# MB_RELAY.net
KiCad netlist of a schematic drawn in Altium Designer
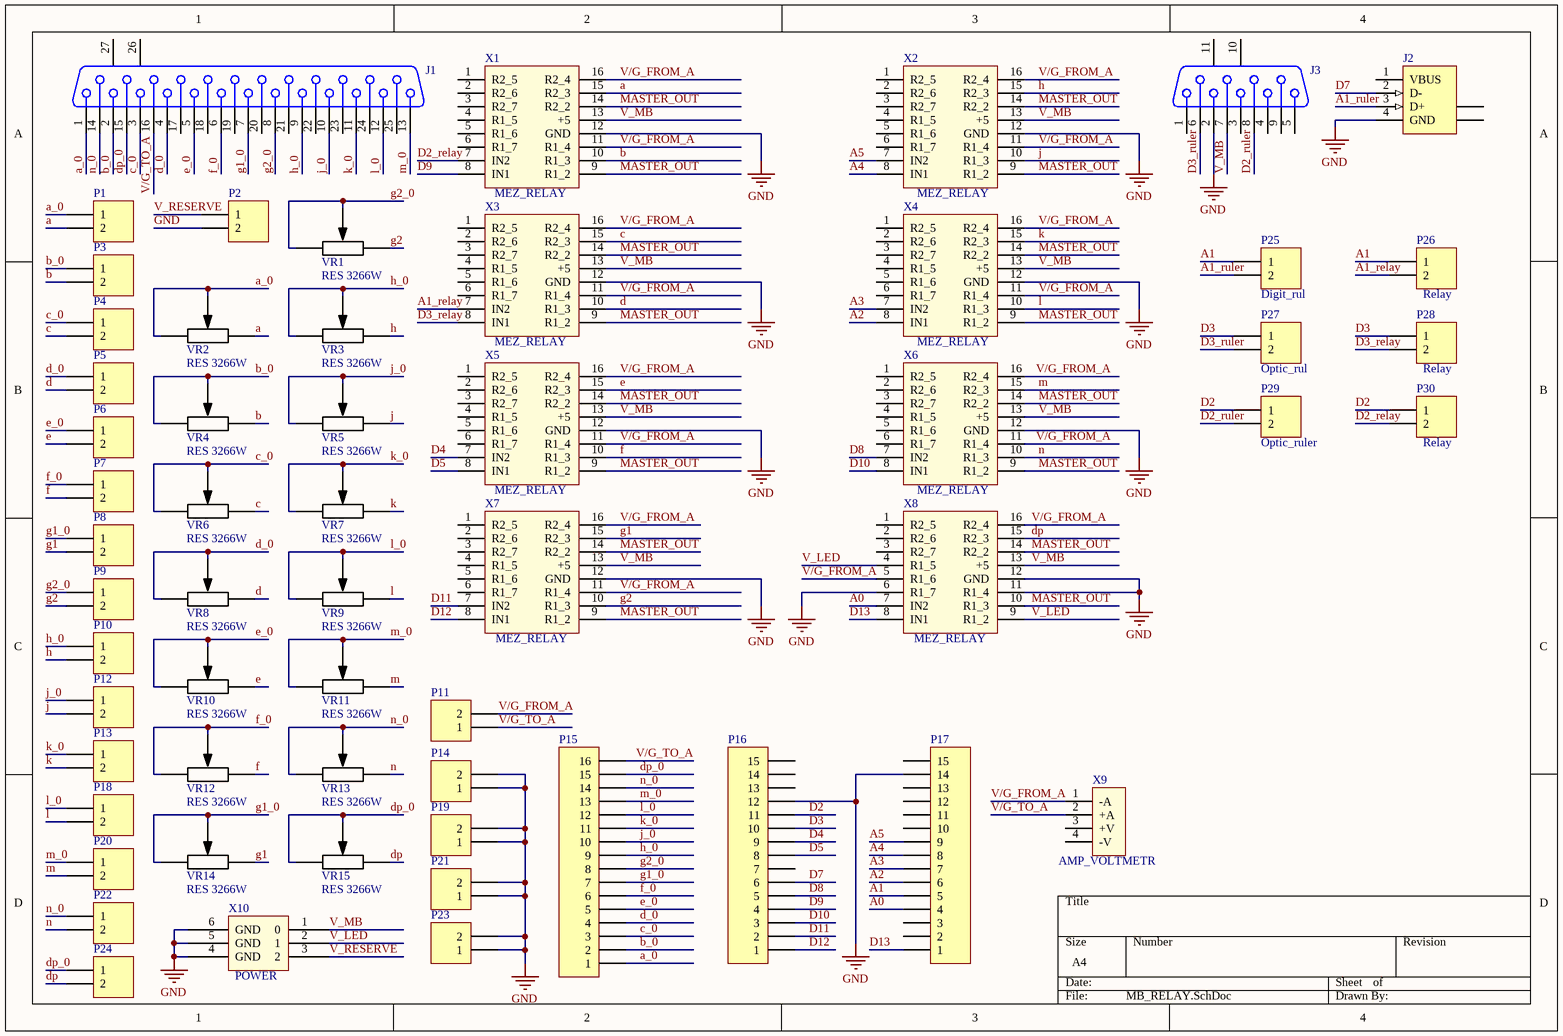
[diagram p0: MB_RELAY.SchDoc]

(export (version "E")
  (design (tool "Eeschema 10.0.6"))
  (components
    (comp (ref "J1")
      (value "D Connector 25")
      (footprint "DSUB1.385-2H25A")
      (description "Receptacle Assembly, 25 Position, Right Angle")
      (fields (field (name "PUBLISHER") "Altium Limited"))
      (libsource (lib "Miscellaneous Connectors") (part "D Connector 25"))
    )
    (comp (ref "J2")
      (value "1-353576-1")
      (footprint "353576")
      (description "USB 1.1, Right Angle, SMT, A Type, Receptacle, 4 Position, White")
      (fields (field (name "PUBLISHER") "Altium Limited"))
      (libsource (lib "AMP Serial Bus USB") (part "1-353576-1"))
    )
    (comp (ref "J3")
      (value "D Connector 9")
      (footprint "DSUB1.385-2H9")
      (description "Receptacle Assembly, 9 Position, Right Angle")
      (fields (field (name "PUBLISHER") "Altium Limited"))
      (libsource (lib "Miscellaneous Connectors") (part "D Connector 9"))
    )
    (comp (ref "P1")
      (value "Header 2")
      (footprint "HDR1X2")
      (description "Header, 2-Pin")
      (fields (field (name "PUBLISHER") "Altium Limited"))
      (libsource (lib "") (part "Header 2_1"))
    )
    (comp (ref "P2")
      (value "Header 2")
      (footprint "HDR1X2")
      (description "Header, 2-Pin")
      (fields (field (name "PUBLISHER") "Altium Limited"))
      (libsource (lib "") (part "Header 2_1"))
    )
    (comp (ref "P3")
      (value "Header 2")
      (footprint "HDR1X2")
      (description "Header, 2-Pin")
      (fields (field (name "PUBLISHER") "Altium Limited"))
      (libsource (lib "") (part "Header 2_1"))
    )
    (comp (ref "P4")
      (value "Header 2")
      (footprint "HDR1X2")
      (description "Header, 2-Pin")
      (fields (field (name "PUBLISHER") "Altium Limited"))
      (libsource (lib "") (part "Header 2_1"))
    )
    (comp (ref "P5")
      (value "Header 2")
      (footprint "HDR1X2")
      (description "Header, 2-Pin")
      (fields (field (name "PUBLISHER") "Altium Limited"))
      (libsource (lib "") (part "Header 2_1"))
    )
    (comp (ref "P6")
      (value "GND")
      (footprint "HDR1X2")
      (description "Header, 2-Pin")
      (fields (field (name "PUBLISHER") "Altium Limited"))
      (libsource (lib "") (part "Header 2_1"))
    )
    (comp (ref "P7")
      (value "GND")
      (footprint "HDR1X2")
      (description "Header, 2-Pin")
      (fields (field (name "PUBLISHER") "Altium Limited"))
      (libsource (lib "") (part "Header 2_1"))
    )
    (comp (ref "P8")
      (value "GND")
      (footprint "HDR1X2")
      (description "Header, 2-Pin")
      (fields (field (name "PUBLISHER") "Altium Limited"))
      (libsource (lib "") (part "Header 2_1"))
    )
    (comp (ref "P9")
      (value "GND")
      (footprint "HDR1X2")
      (description "Header, 2-Pin")
      (fields (field (name "PUBLISHER") "Altium Limited"))
      (libsource (lib "") (part "Header 2_1"))
    )
    (comp (ref "P10")
      (value "Header 2")
      (footprint "HDR1X2")
      (description "Header, 2-Pin")
      (fields (field (name "PUBLISHER") "Altium Limited"))
      (libsource (lib "") (part "Header 2_1"))
    )
    (comp (ref "P11")
      (value "Header 2")
      (footprint "HDR1X2")
      (description "Header, 2-Pin")
      (fields (field (name "PUBLISHER") "Altium Limited"))
      (libsource (lib "Miscellaneous Connectors") (part "Header 2"))
    )
    (comp (ref "P12")
      (value "Header 2")
      (footprint "HDR1X2")
      (description "Header, 2-Pin")
      (fields (field (name "PUBLISHER") "Altium Limited"))
      (libsource (lib "") (part "Header 2_1"))
    )
    (comp (ref "P13")
      (value "GND")
      (footprint "HDR1X2")
      (description "Header, 2-Pin")
      (fields (field (name "PUBLISHER") "Altium Limited"))
      (libsource (lib "") (part "Header 2_1"))
    )
    (comp (ref "P14")
      (value "GND")
      (footprint "HDR1X2")
      (description "Header, 2-Pin")
      (fields (field (name "PUBLISHER") "Altium Limited"))
      (libsource (lib "Miscellaneous Connectors") (part "Header 2"))
    )
    (comp (ref "P15")
      (value "Header 16")
      (footprint "HDR1X16")
      (description "Header, 16-Pin")
      (fields (field (name "PUBLISHER") "Altium Limited"))
      (libsource (lib "Miscellaneous Connectors") (part "Header 16"))
    )
    (comp (ref "P16")
      (value "Header 15")
      (footprint "HDR1X15")
      (description "Header, 15-Pin")
      (fields (field (name "PUBLISHER") "Altium Limited"))
      (libsource (lib "") (part "Header 15_1"))
    )
    (comp (ref "P17")
      (value "Header 15")
      (footprint "HDR1X15")
      (description "Header, 15-Pin")
      (fields (field (name "PUBLISHER") "Altium Limited"))
      (libsource (lib "Miscellaneous Connectors") (part "Header 15"))
    )
    (comp (ref "P18")
      (value "GND")
      (footprint "HDR1X2")
      (description "Header, 2-Pin")
      (fields (field (name "PUBLISHER") "Altium Limited"))
      (libsource (lib "") (part "Header 2_1"))
    )
    (comp (ref "P19")
      (value "GND")
      (footprint "HDR1X2")
      (description "Header, 2-Pin")
      (fields (field (name "PUBLISHER") "Altium Limited"))
      (libsource (lib "Miscellaneous Connectors") (part "Header 2"))
    )
    (comp (ref "P20")
      (value "GND")
      (footprint "HDR1X2")
      (description "Header, 2-Pin")
      (fields (field (name "PUBLISHER") "Altium Limited"))
      (libsource (lib "") (part "Header 2_1"))
    )
    (comp (ref "P21")
      (value "GND")
      (footprint "HDR1X2")
      (description "Header, 2-Pin")
      (fields (field (name "PUBLISHER") "Altium Limited"))
      (libsource (lib "Miscellaneous Connectors") (part "Header 2"))
    )
    (comp (ref "P22")
      (value "GND")
      (footprint "HDR1X2")
      (description "Header, 2-Pin")
      (fields (field (name "PUBLISHER") "Altium Limited"))
      (libsource (lib "") (part "Header 2_1"))
    )
    (comp (ref "P23")
      (value "GND")
      (footprint "HDR1X2")
      (description "Header, 2-Pin")
      (fields (field (name "PUBLISHER") "Altium Limited"))
      (libsource (lib "Miscellaneous Connectors") (part "Header 2"))
    )
    (comp (ref "P24")
      (value "GND")
      (footprint "HDR1X2")
      (description "Header, 2-Pin")
      (fields (field (name "PUBLISHER") "Altium Limited"))
      (libsource (lib "") (part "Header 2_1"))
    )
    (comp (ref "P25")
      (value "Digit_rul")
      (footprint "HDR1X2")
      (description "Header, 2-Pin")
      (fields (field (name "PUBLISHER") "Altium Limited"))
      (libsource (lib "") (part "Header 2_1"))
    )
    (comp (ref "P26")
      (value "Relay")
      (footprint "HDR1X2")
      (description "Header, 2-Pin")
      (fields (field (name "PUBLISHER") "Altium Limited"))
      (libsource (lib "") (part "Header 2_1"))
    )
    (comp (ref "P27")
      (value "Optic_rul")
      (footprint "HDR1X2")
      (description "Header, 2-Pin")
      (fields (field (name "PUBLISHER") "Altium Limited"))
      (libsource (lib "") (part "Header 2_1"))
    )
    (comp (ref "P28")
      (value "Relay")
      (footprint "HDR1X2")
      (description "Header, 2-Pin")
      (fields (field (name "PUBLISHER") "Altium Limited"))
      (libsource (lib "") (part "Header 2_1"))
    )
    (comp (ref "P29")
      (value "Optic_ruler")
      (footprint "HDR1X2")
      (description "Header, 2-Pin")
      (fields (field (name "PUBLISHER") "Altium Limited"))
      (libsource (lib "") (part "Header 2_1"))
    )
    (comp (ref "P30")
      (value "Relay")
      (footprint "HDR1X2")
      (description "Header, 2-Pin")
      (fields (field (name "PUBLISHER") "Altium Limited"))
      (libsource (lib "") (part "Header 2_1"))
    )
    (comp (ref "VR1")
      (value "RES 3266W")
      (footprint "aab_Passive:RES 3266W")
      (libsource (lib "aab_Schlib") (part "RES 3266W"))
    )
    (comp (ref "VR2")
      (value "RES 3266W")
      (footprint "aab_Passive:RES 3266W")
      (libsource (lib "aab_Schlib") (part "RES 3266W"))
    )
    (comp (ref "VR3")
      (value "RES 3266W")
      (footprint "aab_Passive:RES 3266W")
      (libsource (lib "aab_Schlib") (part "RES 3266W"))
    )
    (comp (ref "VR4")
      (value "RES 3266W")
      (footprint "aab_Passive:RES 3266W")
      (libsource (lib "aab_Schlib") (part "RES 3266W"))
    )
    (comp (ref "VR5")
      (value "RES 3266W")
      (footprint "aab_Passive:RES 3266W")
      (libsource (lib "aab_Schlib") (part "RES 3266W"))
    )
    (comp (ref "VR6")
      (value "RES 3266W")
      (footprint "aab_Passive:RES 3266W")
      (libsource (lib "aab_Schlib") (part "RES 3266W"))
    )
    (comp (ref "VR7")
      (value "RES 3266W")
      (footprint "aab_Passive:RES 3266W")
      (libsource (lib "aab_Schlib") (part "RES 3266W"))
    )
    (comp (ref "VR8")
      (value "RES 3266W")
      (footprint "aab_Passive:RES 3266W")
      (libsource (lib "aab_Schlib") (part "RES 3266W"))
    )
    (comp (ref "VR9")
      (value "RES 3266W")
      (footprint "aab_Passive:RES 3266W")
      (libsource (lib "aab_Schlib") (part "RES 3266W"))
    )
    (comp (ref "VR10")
      (value "RES 3266W")
      (footprint "aab_Passive:RES 3266W")
      (libsource (lib "aab_Schlib") (part "RES 3266W"))
    )
    (comp (ref "VR11")
      (value "RES 3266W")
      (footprint "aab_Passive:RES 3266W")
      (libsource (lib "aab_Schlib") (part "RES 3266W"))
    )
    (comp (ref "VR12")
      (value "RES 3266W")
      (footprint "aab_Passive:RES 3266W")
      (libsource (lib "aab_Schlib") (part "RES 3266W"))
    )
    (comp (ref "VR13")
      (value "RES 3266W")
      (footprint "aab_Passive:RES 3266W")
      (libsource (lib "aab_Schlib") (part "RES 3266W"))
    )
    (comp (ref "VR14")
      (value "RES 3266W")
      (footprint "aab_Passive:RES 3266W")
      (libsource (lib "aab_Schlib") (part "RES 3266W"))
    )
    (comp (ref "VR15")
      (value "RES 3266W")
      (footprint "aab_Passive:RES 3266W")
      (libsource (lib "aab_Schlib") (part "RES 3266W"))
    )
    (comp (ref "X1")
      (value "MEZ_RELAY")
      (footprint "MEZ_RELAY")
      (libsource (lib "msp_SchLib") (part "MEZ_RELAY"))
    )
    (comp (ref "X2")
      (value "MEZ_RELAY")
      (footprint "MEZ_RELAY")
      (libsource (lib "msp_SchLib") (part "MEZ_RELAY"))
    )
    (comp (ref "X3")
      (value "MEZ_RELAY")
      (footprint "MEZ_RELAY")
      (libsource (lib "msp_SchLib") (part "MEZ_RELAY"))
    )
    (comp (ref "X4")
      (value "MEZ_RELAY")
      (footprint "MEZ_RELAY")
      (libsource (lib "msp_SchLib") (part "MEZ_RELAY"))
    )
    (comp (ref "X5")
      (value "MEZ_RELAY")
      (footprint "MEZ_RELAY")
      (libsource (lib "msp_SchLib") (part "MEZ_RELAY"))
    )
    (comp (ref "X6")
      (value "MEZ_RELAY")
      (footprint "MEZ_RELAY")
      (libsource (lib "msp_SchLib") (part "MEZ_RELAY"))
    )
    (comp (ref "X7")
      (value "MEZ_RELAY")
      (footprint "MEZ_RELAY")
      (libsource (lib "msp_SchLib") (part "MEZ_RELAY"))
    )
    (comp (ref "X8")
      (value "MEZ_RELAY")
      (footprint "MEZ_RELAY")
      (libsource (lib "msp_SchLib") (part "MEZ_RELAY"))
    )
    (comp (ref "X9")
      (value "AMP_VOLTMETR")
      (footprint "vpl_Passive:AMP_VOLTMETER")
      (libsource (lib "msp_SchLib") (part "AMP_VOLTMETR"))
    )
    (comp (ref "X10")
      (value "POWER")
      (footprint "vpl_Passive:POWER")
      (libsource (lib "msp_SchLib") (part "POWER"))
    )
  )
  (nets
    (net (code "1") (name "/A0") (class "Default")
      (node (ref "P17") (pin "4") (pinfunction "4_4") (pintype "passive"))
      (node (ref "X8") (pin "7") (pinfunction "IN2_7") (pintype "passive"))
    )
    (net (code "2") (name "/A1") (class "Default")
      (node (ref "P17") (pin "5") (pinfunction "5_5") (pintype "passive"))
      (node (ref "P25") (pin "1") (pinfunction "1_1") (pintype "passive"))
      (node (ref "P26") (pin "1") (pinfunction "1_1") (pintype "passive"))
    )
    (net (code "3") (name "/A1_relay") (class "Default")
      (node (ref "P26") (pin "2") (pinfunction "2_2") (pintype "passive"))
      (node (ref "X3") (pin "7") (pinfunction "IN2_7") (pintype "passive"))
    )
    (net (code "4") (name "/A1_ruler") (class "Default")
      (node (ref "J2") (pin "3") (pinfunction "D+_3") (pintype "input"))
      (node (ref "P25") (pin "2") (pinfunction "2_2") (pintype "passive"))
    )
    (net (code "5") (name "/A2") (class "Default")
      (node (ref "P17") (pin "6") (pinfunction "6_6") (pintype "passive"))
      (node (ref "X4") (pin "8") (pinfunction "IN1_8") (pintype "passive"))
    )
    (net (code "6") (name "/A3") (class "Default")
      (node (ref "P17") (pin "7") (pinfunction "7_7") (pintype "passive"))
      (node (ref "X4") (pin "7") (pinfunction "IN2_7") (pintype "passive"))
    )
    (net (code "7") (name "/A4") (class "Default")
      (node (ref "P17") (pin "8") (pinfunction "8_8") (pintype "passive"))
      (node (ref "X2") (pin "8") (pinfunction "IN1_8") (pintype "passive"))
    )
    (net (code "8") (name "/A5") (class "Default")
      (node (ref "P17") (pin "9") (pinfunction "9_9") (pintype "passive"))
      (node (ref "X2") (pin "7") (pinfunction "IN2_7") (pintype "passive"))
    )
    (net (code "9") (name "/D2") (class "Default")
      (node (ref "P16") (pin "11") (pinfunction "11_11") (pintype "passive"))
      (node (ref "P29") (pin "1") (pinfunction "1_1") (pintype "passive"))
      (node (ref "P30") (pin "1") (pinfunction "1_1") (pintype "passive"))
    )
    (net (code "10") (name "/D2_relay") (class "Default")
      (node (ref "P30") (pin "2") (pinfunction "2_2") (pintype "passive"))
      (node (ref "X1") (pin "7") (pinfunction "IN2_7") (pintype "passive"))
    )
    (net (code "11") (name "/D2_ruler") (class "Default")
      (node (ref "J3") (pin "8") (pinfunction "8_8") (pintype "passive"))
      (node (ref "P29") (pin "2") (pinfunction "2_2") (pintype "passive"))
    )
    (net (code "12") (name "/D3") (class "Default")
      (node (ref "P16") (pin "10") (pinfunction "10_10") (pintype "passive"))
      (node (ref "P27") (pin "1") (pinfunction "1_1") (pintype "passive"))
      (node (ref "P28") (pin "1") (pinfunction "1_1") (pintype "passive"))
    )
    (net (code "13") (name "/D3_relay") (class "Default")
      (node (ref "P28") (pin "2") (pinfunction "2_2") (pintype "passive"))
      (node (ref "X3") (pin "8") (pinfunction "IN1_8") (pintype "passive"))
    )
    (net (code "14") (name "/D3_ruler") (class "Default")
      (node (ref "J3") (pin "6") (pinfunction "6_6") (pintype "passive"))
      (node (ref "P27") (pin "2") (pinfunction "2_2") (pintype "passive"))
    )
    (net (code "15") (name "/D4") (class "Default")
      (node (ref "P16") (pin "9") (pinfunction "9_9") (pintype "passive"))
      (node (ref "X5") (pin "7") (pinfunction "IN2_7") (pintype "passive"))
    )
    (net (code "16") (name "/D5") (class "Default")
      (node (ref "P16") (pin "8") (pinfunction "8_8") (pintype "passive"))
      (node (ref "X5") (pin "8") (pinfunction "IN1_8") (pintype "passive"))
    )
    (net (code "17") (name "/D7") (class "Default")
      (node (ref "J2") (pin "2") (pinfunction "D-_2") (pintype "input"))
      (node (ref "P16") (pin "6") (pinfunction "6_6") (pintype "passive"))
    )
    (net (code "18") (name "/D8") (class "Default")
      (node (ref "P16") (pin "5") (pinfunction "5_5") (pintype "passive"))
      (node (ref "X6") (pin "7") (pinfunction "IN2_7") (pintype "passive"))
    )
    (net (code "19") (name "/D9") (class "Default")
      (node (ref "P16") (pin "4") (pinfunction "4_4") (pintype "passive"))
      (node (ref "X1") (pin "8") (pinfunction "IN1_8") (pintype "passive"))
    )
    (net (code "20") (name "/D10") (class "Default")
      (node (ref "P16") (pin "3") (pinfunction "3_3") (pintype "passive"))
      (node (ref "X6") (pin "8") (pinfunction "IN1_8") (pintype "passive"))
    )
    (net (code "21") (name "/D11") (class "Default")
      (node (ref "P16") (pin "2") (pinfunction "2_2") (pintype "passive"))
      (node (ref "X7") (pin "7") (pinfunction "IN2_7") (pintype "passive"))
    )
    (net (code "22") (name "/D12") (class "Default")
      (node (ref "P16") (pin "1") (pinfunction "1_1") (pintype "passive"))
      (node (ref "X7") (pin "8") (pinfunction "IN1_8") (pintype "passive"))
    )
    (net (code "23") (name "/D13") (class "Default")
      (node (ref "P17") (pin "1") (pinfunction "1_1") (pintype "passive"))
      (node (ref "X8") (pin "8") (pinfunction "IN1_8") (pintype "passive"))
    )
    (net (code "24") (name "/MASTER_OUT") (class "Default")
      (node (ref "X1") (pin "14") (pinfunction "R2_2_14") (pintype "passive"))
      (node (ref "X1") (pin "9") (pinfunction "R1_2_9") (pintype "passive"))
      (node (ref "X2") (pin "14") (pinfunction "R2_2_14") (pintype "passive"))
      (node (ref "X2") (pin "9") (pinfunction "R1_2_9") (pintype "passive"))
      (node (ref "X3") (pin "14") (pinfunction "R2_2_14") (pintype "passive"))
      (node (ref "X3") (pin "9") (pinfunction "R1_2_9") (pintype "passive"))
      (node (ref "X4") (pin "14") (pinfunction "R2_2_14") (pintype "passive"))
      (node (ref "X4") (pin "9") (pinfunction "R1_2_9") (pintype "passive"))
      (node (ref "X5") (pin "14") (pinfunction "R2_2_14") (pintype "passive"))
      (node (ref "X5") (pin "9") (pinfunction "R1_2_9") (pintype "passive"))
      (node (ref "X6") (pin "14") (pinfunction "R2_2_14") (pintype "passive"))
      (node (ref "X6") (pin "9") (pinfunction "R1_2_9") (pintype "passive"))
      (node (ref "X7") (pin "14") (pinfunction "R2_2_14") (pintype "passive"))
      (node (ref "X7") (pin "9") (pinfunction "R1_2_9") (pintype "passive"))
      (node (ref "X8") (pin "10") (pinfunction "R1_3_10") (pintype "passive"))
      (node (ref "X8") (pin "14") (pinfunction "R2_2_14") (pintype "passive"))
    )
    (net (code "25") (name "/V_LED") (class "Default")
      (node (ref "X10") (pin "2") (pinfunction "1_2") (pintype "passive"))
      (node (ref "X8") (pin "4") (pinfunction "R1_5_4") (pintype "passive"))
      (node (ref "X8") (pin "9") (pinfunction "R1_2_9") (pintype "passive"))
    )
    (net (code "26") (name "/V_MB") (class "Default")
      (node (ref "J3") (pin "7") (pinfunction "7_7") (pintype "passive"))
      (node (ref "X1") (pin "13") (pinfunction "+5_13") (pintype "passive"))
      (node (ref "X10") (pin "1") (pinfunction "0_1") (pintype "passive"))
      (node (ref "X2") (pin "13") (pinfunction "+5_13") (pintype "passive"))
      (node (ref "X3") (pin "13") (pinfunction "+5_13") (pintype "passive"))
      (node (ref "X4") (pin "13") (pinfunction "+5_13") (pintype "passive"))
      (node (ref "X5") (pin "13") (pinfunction "+5_13") (pintype "passive"))
      (node (ref "X6") (pin "13") (pinfunction "+5_13") (pintype "passive"))
      (node (ref "X7") (pin "13") (pinfunction "+5_13") (pintype "passive"))
      (node (ref "X8") (pin "13") (pinfunction "+5_13") (pintype "passive"))
    )
    (net (code "27") (name "/V_RESERVE") (class "Default")
      (node (ref "P2") (pin "1") (pinfunction "1_1") (pintype "passive"))
      (node (ref "X10") (pin "3") (pinfunction "2_3") (pintype "passive"))
    )
    (net (code "28") (name "/V{slash}G_FROM_A") (class "Default")
      (node (ref "P11") (pin "2") (pinfunction "2_2") (pintype "passive"))
      (node (ref "X1") (pin "11") (pinfunction "R1_4_11") (pintype "passive"))
      (node (ref "X1") (pin "16") (pinfunction "R2_4_16") (pintype "passive"))
      (node (ref "X2") (pin "11") (pinfunction "R1_4_11") (pintype "passive"))
      (node (ref "X2") (pin "16") (pinfunction "R2_4_16") (pintype "passive"))
      (node (ref "X3") (pin "11") (pinfunction "R1_4_11") (pintype "passive"))
      (node (ref "X3") (pin "16") (pinfunction "R2_4_16") (pintype "passive"))
      (node (ref "X4") (pin "11") (pinfunction "R1_4_11") (pintype "passive"))
      (node (ref "X4") (pin "16") (pinfunction "R2_4_16") (pintype "passive"))
      (node (ref "X5") (pin "11") (pinfunction "R1_4_11") (pintype "passive"))
      (node (ref "X5") (pin "16") (pinfunction "R2_4_16") (pintype "passive"))
      (node (ref "X6") (pin "11") (pinfunction "R1_4_11") (pintype "passive"))
      (node (ref "X6") (pin "16") (pinfunction "R2_4_16") (pintype "passive"))
      (node (ref "X7") (pin "11") (pinfunction "R1_4_11") (pintype "passive"))
      (node (ref "X7") (pin "16") (pinfunction "R2_4_16") (pintype "passive"))
      (node (ref "X8") (pin "16") (pinfunction "R2_4_16") (pintype "passive"))
      (node (ref "X8") (pin "5") (pinfunction "R1_6_5") (pintype "passive"))
      (node (ref "X9") (pin "1") (pinfunction "-A_1") (pintype "passive"))
    )
    (net (code "29") (name "/V{slash}G_TO_A") (class "Default")
      (node (ref "J1") (pin "16") (pinfunction "16_16") (pintype "passive"))
      (node (ref "P11") (pin "1") (pinfunction "1_1") (pintype "passive"))
      (node (ref "P15") (pin "16") (pinfunction "16_16") (pintype "passive"))
      (node (ref "X9") (pin "2") (pinfunction "+A_2") (pintype "passive"))
    )
    (net (code "30") (name "/a") (class "Default")
      (node (ref "P1") (pin "2") (pinfunction "2_2") (pintype "passive"))
      (node (ref "VR2") (pin "3") (pinfunction "3_3") (pintype "passive"))
      (node (ref "X1") (pin "15") (pinfunction "R2_3_15") (pintype "passive"))
    )
    (net (code "31") (name "/a_0") (class "Default")
      (node (ref "J1") (pin "1") (pinfunction "1_1") (pintype "passive"))
      (node (ref "P1") (pin "1") (pinfunction "1_1") (pintype "passive"))
      (node (ref "P15") (pin "1") (pinfunction "1_1") (pintype "passive"))
      (node (ref "VR2") (pin "1") (pinfunction "1_1") (pintype "passive"))
      (node (ref "VR2") (pin "2") (pinfunction "2_2") (pintype "passive"))
    )
    (net (code "32") (name "/b") (class "Default")
      (node (ref "P3") (pin "2") (pinfunction "2_2") (pintype "passive"))
      (node (ref "VR4") (pin "3") (pinfunction "3_3") (pintype "passive"))
      (node (ref "X1") (pin "10") (pinfunction "R1_3_10") (pintype "passive"))
    )
    (net (code "33") (name "/b_0") (class "Default")
      (node (ref "J1") (pin "2") (pinfunction "2_2") (pintype "passive"))
      (node (ref "P15") (pin "2") (pinfunction "2_2") (pintype "passive"))
      (node (ref "P3") (pin "1") (pinfunction "1_1") (pintype "passive"))
      (node (ref "VR4") (pin "1") (pinfunction "1_1") (pintype "passive"))
      (node (ref "VR4") (pin "2") (pinfunction "2_2") (pintype "passive"))
    )
    (net (code "34") (name "/c") (class "Default")
      (node (ref "P4") (pin "2") (pinfunction "2_2") (pintype "passive"))
      (node (ref "VR6") (pin "3") (pinfunction "3_3") (pintype "passive"))
      (node (ref "X3") (pin "15") (pinfunction "R2_3_15") (pintype "passive"))
    )
    (net (code "35") (name "/c_0") (class "Default")
      (node (ref "J1") (pin "3") (pinfunction "3_3") (pintype "passive"))
      (node (ref "P15") (pin "3") (pinfunction "3_3") (pintype "passive"))
      (node (ref "P4") (pin "1") (pinfunction "1_1") (pintype "passive"))
      (node (ref "VR6") (pin "1") (pinfunction "1_1") (pintype "passive"))
      (node (ref "VR6") (pin "2") (pinfunction "2_2") (pintype "passive"))
    )
    (net (code "36") (name "/d") (class "Default")
      (node (ref "P5") (pin "2") (pinfunction "2_2") (pintype "passive"))
      (node (ref "VR8") (pin "3") (pinfunction "3_3") (pintype "passive"))
      (node (ref "X3") (pin "10") (pinfunction "R1_3_10") (pintype "passive"))
    )
    (net (code "37") (name "/d_0") (class "Default")
      (node (ref "J1") (pin "4") (pinfunction "4_4") (pintype "passive"))
      (node (ref "P15") (pin "4") (pinfunction "4_4") (pintype "passive"))
      (node (ref "P5") (pin "1") (pinfunction "1_1") (pintype "passive"))
      (node (ref "VR8") (pin "1") (pinfunction "1_1") (pintype "passive"))
      (node (ref "VR8") (pin "2") (pinfunction "2_2") (pintype "passive"))
    )
    (net (code "38") (name "/dp") (class "Default")
      (node (ref "P24") (pin "2") (pinfunction "2_2") (pintype "passive"))
      (node (ref "VR15") (pin "3") (pinfunction "3_3") (pintype "passive"))
      (node (ref "X8") (pin "15") (pinfunction "R2_3_15") (pintype "passive"))
    )
    (net (code "39") (name "/dp_0") (class "Default")
      (node (ref "J1") (pin "15") (pinfunction "15_15") (pintype "passive"))
      (node (ref "P15") (pin "15") (pinfunction "15_15") (pintype "passive"))
      (node (ref "P24") (pin "1") (pinfunction "1_1") (pintype "passive"))
      (node (ref "VR15") (pin "1") (pinfunction "1_1") (pintype "passive"))
      (node (ref "VR15") (pin "2") (pinfunction "2_2") (pintype "passive"))
    )
    (net (code "40") (name "/e") (class "Default")
      (node (ref "P6") (pin "2") (pinfunction "2_2") (pintype "passive"))
      (node (ref "VR10") (pin "3") (pinfunction "3_3") (pintype "passive"))
      (node (ref "X5") (pin "15") (pinfunction "R2_3_15") (pintype "passive"))
    )
    (net (code "41") (name "/e_0") (class "Default")
      (node (ref "J1") (pin "5") (pinfunction "5_5") (pintype "passive"))
      (node (ref "P15") (pin "5") (pinfunction "5_5") (pintype "passive"))
      (node (ref "P6") (pin "1") (pinfunction "1_1") (pintype "passive"))
      (node (ref "VR10") (pin "1") (pinfunction "1_1") (pintype "passive"))
      (node (ref "VR10") (pin "2") (pinfunction "2_2") (pintype "passive"))
    )
    (net (code "42") (name "/f") (class "Default")
      (node (ref "P7") (pin "2") (pinfunction "2_2") (pintype "passive"))
      (node (ref "VR12") (pin "3") (pinfunction "3_3") (pintype "passive"))
      (node (ref "X5") (pin "10") (pinfunction "R1_3_10") (pintype "passive"))
    )
    (net (code "43") (name "/f_0") (class "Default")
      (node (ref "J1") (pin "6") (pinfunction "6_6") (pintype "passive"))
      (node (ref "P15") (pin "6") (pinfunction "6_6") (pintype "passive"))
      (node (ref "P7") (pin "1") (pinfunction "1_1") (pintype "passive"))
      (node (ref "VR12") (pin "1") (pinfunction "1_1") (pintype "passive"))
      (node (ref "VR12") (pin "2") (pinfunction "2_2") (pintype "passive"))
    )
    (net (code "44") (name "/g1") (class "Default")
      (node (ref "P8") (pin "2") (pinfunction "2_2") (pintype "passive"))
      (node (ref "VR14") (pin "3") (pinfunction "3_3") (pintype "passive"))
      (node (ref "X7") (pin "15") (pinfunction "R2_3_15") (pintype "passive"))
    )
    (net (code "45") (name "/g1_0") (class "Default")
      (node (ref "J1") (pin "7") (pinfunction "7_7") (pintype "passive"))
      (node (ref "P15") (pin "7") (pinfunction "7_7") (pintype "passive"))
      (node (ref "P8") (pin "1") (pinfunction "1_1") (pintype "passive"))
      (node (ref "VR14") (pin "1") (pinfunction "1_1") (pintype "passive"))
      (node (ref "VR14") (pin "2") (pinfunction "2_2") (pintype "passive"))
    )
    (net (code "46") (name "/g2") (class "Default")
      (node (ref "P9") (pin "2") (pinfunction "2_2") (pintype "passive"))
      (node (ref "VR1") (pin "3") (pinfunction "3_3") (pintype "passive"))
      (node (ref "X7") (pin "10") (pinfunction "R1_3_10") (pintype "passive"))
    )
    (net (code "47") (name "/g2_0") (class "Default")
      (node (ref "J1") (pin "8") (pinfunction "8_8") (pintype "passive"))
      (node (ref "P15") (pin "8") (pinfunction "8_8") (pintype "passive"))
      (node (ref "P9") (pin "1") (pinfunction "1_1") (pintype "passive"))
      (node (ref "VR1") (pin "1") (pinfunction "1_1") (pintype "passive"))
      (node (ref "VR1") (pin "2") (pinfunction "2_2") (pintype "passive"))
    )
    (net (code "48") (name "/h") (class "Default")
      (node (ref "P10") (pin "2") (pinfunction "2_2") (pintype "passive"))
      (node (ref "VR3") (pin "3") (pinfunction "3_3") (pintype "passive"))
      (node (ref "X2") (pin "15") (pinfunction "R2_3_15") (pintype "passive"))
    )
    (net (code "49") (name "/h_0") (class "Default")
      (node (ref "J1") (pin "9") (pinfunction "9_9") (pintype "passive"))
      (node (ref "P10") (pin "1") (pinfunction "1_1") (pintype "passive"))
      (node (ref "P15") (pin "9") (pinfunction "9_9") (pintype "passive"))
      (node (ref "VR3") (pin "1") (pinfunction "1_1") (pintype "passive"))
      (node (ref "VR3") (pin "2") (pinfunction "2_2") (pintype "passive"))
    )
    (net (code "50") (name "/j") (class "Default")
      (node (ref "P12") (pin "2") (pinfunction "2_2") (pintype "passive"))
      (node (ref "VR5") (pin "3") (pinfunction "3_3") (pintype "passive"))
      (node (ref "X2") (pin "10") (pinfunction "R1_3_10") (pintype "passive"))
    )
    (net (code "51") (name "/j_0") (class "Default")
      (node (ref "J1") (pin "10") (pinfunction "10_10") (pintype "passive"))
      (node (ref "P12") (pin "1") (pinfunction "1_1") (pintype "passive"))
      (node (ref "P15") (pin "10") (pinfunction "10_10") (pintype "passive"))
      (node (ref "VR5") (pin "1") (pinfunction "1_1") (pintype "passive"))
      (node (ref "VR5") (pin "2") (pinfunction "2_2") (pintype "passive"))
    )
    (net (code "52") (name "/k") (class "Default")
      (node (ref "P13") (pin "2") (pinfunction "2_2") (pintype "passive"))
      (node (ref "VR7") (pin "3") (pinfunction "3_3") (pintype "passive"))
      (node (ref "X4") (pin "15") (pinfunction "R2_3_15") (pintype "passive"))
    )
    (net (code "53") (name "/k_0") (class "Default")
      (node (ref "J1") (pin "11") (pinfunction "11_11") (pintype "passive"))
      (node (ref "P13") (pin "1") (pinfunction "1_1") (pintype "passive"))
      (node (ref "P15") (pin "11") (pinfunction "11_11") (pintype "passive"))
      (node (ref "VR7") (pin "1") (pinfunction "1_1") (pintype "passive"))
      (node (ref "VR7") (pin "2") (pinfunction "2_2") (pintype "passive"))
    )
    (net (code "54") (name "/l") (class "Default")
      (node (ref "P18") (pin "2") (pinfunction "2_2") (pintype "passive"))
      (node (ref "VR9") (pin "3") (pinfunction "3_3") (pintype "passive"))
      (node (ref "X4") (pin "10") (pinfunction "R1_3_10") (pintype "passive"))
    )
    (net (code "55") (name "/l_0") (class "Default")
      (node (ref "J1") (pin "12") (pinfunction "12_12") (pintype "passive"))
      (node (ref "P15") (pin "12") (pinfunction "12_12") (pintype "passive"))
      (node (ref "P18") (pin "1") (pinfunction "1_1") (pintype "passive"))
      (node (ref "VR9") (pin "1") (pinfunction "1_1") (pintype "passive"))
      (node (ref "VR9") (pin "2") (pinfunction "2_2") (pintype "passive"))
    )
    (net (code "56") (name "/m") (class "Default")
      (node (ref "P20") (pin "2") (pinfunction "2_2") (pintype "passive"))
      (node (ref "VR11") (pin "3") (pinfunction "3_3") (pintype "passive"))
      (node (ref "X6") (pin "15") (pinfunction "R2_3_15") (pintype "passive"))
    )
    (net (code "57") (name "/m_0") (class "Default")
      (node (ref "J1") (pin "13") (pinfunction "13_13") (pintype "passive"))
      (node (ref "P15") (pin "13") (pinfunction "13_13") (pintype "passive"))
      (node (ref "P20") (pin "1") (pinfunction "1_1") (pintype "passive"))
      (node (ref "VR11") (pin "1") (pinfunction "1_1") (pintype "passive"))
      (node (ref "VR11") (pin "2") (pinfunction "2_2") (pintype "passive"))
    )
    (net (code "58") (name "/n") (class "Default")
      (node (ref "P22") (pin "2") (pinfunction "2_2") (pintype "passive"))
      (node (ref "VR13") (pin "3") (pinfunction "3_3") (pintype "passive"))
      (node (ref "X6") (pin "10") (pinfunction "R1_3_10") (pintype "passive"))
    )
    (net (code "59") (name "/n_0") (class "Default")
      (node (ref "J1") (pin "14") (pinfunction "14_14") (pintype "passive"))
      (node (ref "P15") (pin "14") (pinfunction "14_14") (pintype "passive"))
      (node (ref "P22") (pin "1") (pinfunction "1_1") (pintype "passive"))
      (node (ref "VR13") (pin "1") (pinfunction "1_1") (pintype "passive"))
      (node (ref "VR13") (pin "2") (pinfunction "2_2") (pintype "passive"))
    )
    (net (code "60") (name "GND") (class "Default")
      (node (ref "J2") (pin "4") (pinfunction "GND_4") (pintype "power_in"))
      (node (ref "J3") (pin "2") (pinfunction "2_2") (pintype "passive"))
      (node (ref "P14") (pin "1") (pinfunction "1_1") (pintype "passive"))
      (node (ref "P14") (pin "2") (pinfunction "2_2") (pintype "passive"))
      (node (ref "P16") (pin "12") (pinfunction "12_12") (pintype "passive"))
      (node (ref "P17") (pin "14") (pinfunction "14_14") (pintype "passive"))
      (node (ref "P19") (pin "1") (pinfunction "1_1") (pintype "passive"))
      (node (ref "P19") (pin "2") (pinfunction "2_2") (pintype "passive"))
      (node (ref "P2") (pin "2") (pinfunction "2_2") (pintype "passive"))
      (node (ref "P21") (pin "1") (pinfunction "1_1") (pintype "passive"))
      (node (ref "P21") (pin "2") (pinfunction "2_2") (pintype "passive"))
      (node (ref "P23") (pin "1") (pinfunction "1_1") (pintype "passive"))
      (node (ref "P23") (pin "2") (pinfunction "2_2") (pintype "passive"))
      (node (ref "X1") (pin "12") (pinfunction "GND_12") (pintype "passive"))
      (node (ref "X10") (pin "4") (pinfunction "GND_4") (pintype "passive"))
      (node (ref "X10") (pin "5") (pinfunction "GND_5") (pintype "passive"))
      (node (ref "X10") (pin "6") (pinfunction "GND_6") (pintype "passive"))
      (node (ref "X2") (pin "12") (pinfunction "GND_12") (pintype "passive"))
      (node (ref "X3") (pin "12") (pinfunction "GND_12") (pintype "passive"))
      (node (ref "X4") (pin "12") (pinfunction "GND_12") (pintype "passive"))
      (node (ref "X5") (pin "12") (pinfunction "GND_12") (pintype "passive"))
      (node (ref "X6") (pin "12") (pinfunction "GND_12") (pintype "passive"))
      (node (ref "X7") (pin "12") (pinfunction "GND_12") (pintype "passive"))
      (node (ref "X8") (pin "11") (pinfunction "R1_4_11") (pintype "passive"))
      (node (ref "X8") (pin "12") (pinfunction "GND_12") (pintype "passive"))
      (node (ref "X8") (pin "6") (pinfunction "R1_7_6") (pintype "passive"))
    )
    (net (code "61") (name "unconnected-(J1-MH1-Pad26)") (class "Default")
      (node (ref "J1") (pin "26") (pinfunction "MH1_26") (pintype "passive"))
    )
    (net (code "62") (name "unconnected-(J1-MH2-Pad27)") (class "Default")
      (node (ref "J1") (pin "27") (pinfunction "MH2_27") (pintype "passive"))
    )
    (net (code "63") (name "unconnected-(J1-Pad17)") (class "Default")
      (node (ref "J1") (pin "17") (pinfunction "17_17") (pintype "passive"))
    )
    (net (code "64") (name "unconnected-(J1-Pad18)") (class "Default")
      (node (ref "J1") (pin "18") (pinfunction "18_18") (pintype "passive"))
    )
    (net (code "65") (name "unconnected-(J1-Pad19)") (class "Default")
      (node (ref "J1") (pin "19") (pinfunction "19_19") (pintype "passive"))
    )
    (net (code "66") (name "unconnected-(J1-Pad20)") (class "Default")
      (node (ref "J1") (pin "20") (pinfunction "20_20") (pintype "passive"))
    )
    (net (code "67") (name "unconnected-(J1-Pad21)") (class "Default")
      (node (ref "J1") (pin "21") (pinfunction "21_21") (pintype "passive"))
    )
    (net (code "68") (name "unconnected-(J1-Pad22)") (class "Default")
      (node (ref "J1") (pin "22") (pinfunction "22_22") (pintype "passive"))
    )
    (net (code "69") (name "unconnected-(J1-Pad23)") (class "Default")
      (node (ref "J1") (pin "23") (pinfunction "23_23") (pintype "passive"))
    )
    (net (code "70") (name "unconnected-(J1-Pad24)") (class "Default")
      (node (ref "J1") (pin "24") (pinfunction "24_24") (pintype "passive"))
    )
    (net (code "71") (name "unconnected-(J1-Pad25)") (class "Default")
      (node (ref "J1") (pin "25") (pinfunction "25_25") (pintype "passive"))
    )
    (net (code "72") (name "unconnected-(J2-SHLD-Pad5)") (class "Default")
      (node (ref "J2") (pin "5") (pinfunction "SHLD_5") (pintype "passive"))
    )
    (net (code "73") (name "unconnected-(J2-SHLD-Pad6)") (class "Default")
      (node (ref "J2") (pin "6") (pinfunction "SHLD_6") (pintype "passive"))
    )
    (net (code "74") (name "unconnected-(J2-VBUS-Pad1)") (class "Default")
      (node (ref "J2") (pin "1") (pinfunction "VBUS_1") (pintype "power_in"))
    )
    (net (code "75") (name "unconnected-(J3-MH1-Pad10)") (class "Default")
      (node (ref "J3") (pin "10") (pinfunction "MH1_10") (pintype "passive"))
    )
    (net (code "76") (name "unconnected-(J3-MH2-Pad11)") (class "Default")
      (node (ref "J3") (pin "11") (pinfunction "MH2_11") (pintype "passive"))
    )
    (net (code "77") (name "unconnected-(J3-Pad1)") (class "Default")
      (node (ref "J3") (pin "1") (pinfunction "1_1") (pintype "passive"))
    )
    (net (code "78") (name "unconnected-(J3-Pad3)") (class "Default")
      (node (ref "J3") (pin "3") (pinfunction "3_3") (pintype "passive"))
    )
    (net (code "79") (name "unconnected-(J3-Pad4)") (class "Default")
      (node (ref "J3") (pin "4") (pinfunction "4_4") (pintype "passive"))
    )
    (net (code "80") (name "unconnected-(J3-Pad5)") (class "Default")
      (node (ref "J3") (pin "5") (pinfunction "5_5") (pintype "passive"))
    )
    (net (code "81") (name "unconnected-(J3-Pad9)") (class "Default")
      (node (ref "J3") (pin "9") (pinfunction "9_9") (pintype "passive"))
    )
    (net (code "82") (name "unconnected-(P16-Pad7)") (class "Default")
      (node (ref "P16") (pin "7") (pinfunction "7_7") (pintype "passive"))
    )
    (net (code "83") (name "unconnected-(P16-Pad13)") (class "Default")
      (node (ref "P16") (pin "13") (pinfunction "13_13") (pintype "passive"))
    )
    (net (code "84") (name "unconnected-(P16-Pad14)") (class "Default")
      (node (ref "P16") (pin "14") (pinfunction "14_14") (pintype "passive"))
    )
    (net (code "85") (name "unconnected-(P16-Pad15)") (class "Default")
      (node (ref "P16") (pin "15") (pinfunction "15_15") (pintype "passive"))
    )
    (net (code "86") (name "unconnected-(P17-Pad2)") (class "Default")
      (node (ref "P17") (pin "2") (pinfunction "2_2") (pintype "passive"))
    )
    (net (code "87") (name "unconnected-(P17-Pad3)") (class "Default")
      (node (ref "P17") (pin "3") (pinfunction "3_3") (pintype "passive"))
    )
    (net (code "88") (name "unconnected-(P17-Pad10)") (class "Default")
      (node (ref "P17") (pin "10") (pinfunction "10_10") (pintype "passive"))
    )
    (net (code "89") (name "unconnected-(P17-Pad11)") (class "Default")
      (node (ref "P17") (pin "11") (pinfunction "11_11") (pintype "passive"))
    )
    (net (code "90") (name "unconnected-(P17-Pad12)") (class "Default")
      (node (ref "P17") (pin "12") (pinfunction "12_12") (pintype "passive"))
    )
    (net (code "91") (name "unconnected-(P17-Pad13)") (class "Default")
      (node (ref "P17") (pin "13") (pinfunction "13_13") (pintype "passive"))
    )
    (net (code "92") (name "unconnected-(P17-Pad15)") (class "Default")
      (node (ref "P17") (pin "15") (pinfunction "15_15") (pintype "passive"))
    )
    (net (code "93") (name "unconnected-(X1-R1_5-Pad4)") (class "Default")
      (node (ref "X1") (pin "4") (pinfunction "R1_5_4") (pintype "passive"))
    )
    (net (code "94") (name "unconnected-(X1-R1_6-Pad5)") (class "Default")
      (node (ref "X1") (pin "5") (pinfunction "R1_6_5") (pintype "passive"))
    )
    (net (code "95") (name "unconnected-(X1-R1_7-Pad6)") (class "Default")
      (node (ref "X1") (pin "6") (pinfunction "R1_7_6") (pintype "passive"))
    )
    (net (code "96") (name "unconnected-(X1-R2_5-Pad1)") (class "Default")
      (node (ref "X1") (pin "1") (pinfunction "R2_5_1") (pintype "passive"))
    )
    (net (code "97") (name "unconnected-(X1-R2_6-Pad2)") (class "Default")
      (node (ref "X1") (pin "2") (pinfunction "R2_6_2") (pintype "passive"))
    )
    (net (code "98") (name "unconnected-(X1-R2_7-Pad3)") (class "Default")
      (node (ref "X1") (pin "3") (pinfunction "R2_7_3") (pintype "passive"))
    )
    (net (code "99") (name "unconnected-(X2-R1_5-Pad4)") (class "Default")
      (node (ref "X2") (pin "4") (pinfunction "R1_5_4") (pintype "passive"))
    )
    (net (code "100") (name "unconnected-(X2-R1_6-Pad5)") (class "Default")
      (node (ref "X2") (pin "5") (pinfunction "R1_6_5") (pintype "passive"))
    )
    (net (code "101") (name "unconnected-(X2-R1_7-Pad6)") (class "Default")
      (node (ref "X2") (pin "6") (pinfunction "R1_7_6") (pintype "passive"))
    )
    (net (code "102") (name "unconnected-(X2-R2_5-Pad1)") (class "Default")
      (node (ref "X2") (pin "1") (pinfunction "R2_5_1") (pintype "passive"))
    )
    (net (code "103") (name "unconnected-(X2-R2_6-Pad2)") (class "Default")
      (node (ref "X2") (pin "2") (pinfunction "R2_6_2") (pintype "passive"))
    )
    (net (code "104") (name "unconnected-(X2-R2_7-Pad3)") (class "Default")
      (node (ref "X2") (pin "3") (pinfunction "R2_7_3") (pintype "passive"))
    )
    (net (code "105") (name "unconnected-(X3-R1_5-Pad4)") (class "Default")
      (node (ref "X3") (pin "4") (pinfunction "R1_5_4") (pintype "passive"))
    )
    (net (code "106") (name "unconnected-(X3-R1_6-Pad5)") (class "Default")
      (node (ref "X3") (pin "5") (pinfunction "R1_6_5") (pintype "passive"))
    )
    (net (code "107") (name "unconnected-(X3-R1_7-Pad6)") (class "Default")
      (node (ref "X3") (pin "6") (pinfunction "R1_7_6") (pintype "passive"))
    )
    (net (code "108") (name "unconnected-(X3-R2_5-Pad1)") (class "Default")
      (node (ref "X3") (pin "1") (pinfunction "R2_5_1") (pintype "passive"))
    )
    (net (code "109") (name "unconnected-(X3-R2_6-Pad2)") (class "Default")
      (node (ref "X3") (pin "2") (pinfunction "R2_6_2") (pintype "passive"))
    )
    (net (code "110") (name "unconnected-(X3-R2_7-Pad3)") (class "Default")
      (node (ref "X3") (pin "3") (pinfunction "R2_7_3") (pintype "passive"))
    )
    (net (code "111") (name "unconnected-(X4-R1_5-Pad4)") (class "Default")
      (node (ref "X4") (pin "4") (pinfunction "R1_5_4") (pintype "passive"))
    )
    (net (code "112") (name "unconnected-(X4-R1_6-Pad5)") (class "Default")
      (node (ref "X4") (pin "5") (pinfunction "R1_6_5") (pintype "passive"))
    )
    (net (code "113") (name "unconnected-(X4-R1_7-Pad6)") (class "Default")
      (node (ref "X4") (pin "6") (pinfunction "R1_7_6") (pintype "passive"))
    )
    (net (code "114") (name "unconnected-(X4-R2_5-Pad1)") (class "Default")
      (node (ref "X4") (pin "1") (pinfunction "R2_5_1") (pintype "passive"))
    )
    (net (code "115") (name "unconnected-(X4-R2_6-Pad2)") (class "Default")
      (node (ref "X4") (pin "2") (pinfunction "R2_6_2") (pintype "passive"))
    )
    (net (code "116") (name "unconnected-(X4-R2_7-Pad3)") (class "Default")
      (node (ref "X4") (pin "3") (pinfunction "R2_7_3") (pintype "passive"))
    )
    (net (code "117") (name "unconnected-(X5-R1_5-Pad4)") (class "Default")
      (node (ref "X5") (pin "4") (pinfunction "R1_5_4") (pintype "passive"))
    )
    (net (code "118") (name "unconnected-(X5-R1_6-Pad5)") (class "Default")
      (node (ref "X5") (pin "5") (pinfunction "R1_6_5") (pintype "passive"))
    )
    (net (code "119") (name "unconnected-(X5-R1_7-Pad6)") (class "Default")
      (node (ref "X5") (pin "6") (pinfunction "R1_7_6") (pintype "passive"))
    )
    (net (code "120") (name "unconnected-(X5-R2_5-Pad1)") (class "Default")
      (node (ref "X5") (pin "1") (pinfunction "R2_5_1") (pintype "passive"))
    )
    (net (code "121") (name "unconnected-(X5-R2_6-Pad2)") (class "Default")
      (node (ref "X5") (pin "2") (pinfunction "R2_6_2") (pintype "passive"))
    )
    (net (code "122") (name "unconnected-(X5-R2_7-Pad3)") (class "Default")
      (node (ref "X5") (pin "3") (pinfunction "R2_7_3") (pintype "passive"))
    )
    (net (code "123") (name "unconnected-(X6-R1_5-Pad4)") (class "Default")
      (node (ref "X6") (pin "4") (pinfunction "R1_5_4") (pintype "passive"))
    )
    (net (code "124") (name "unconnected-(X6-R1_6-Pad5)") (class "Default")
      (node (ref "X6") (pin "5") (pinfunction "R1_6_5") (pintype "passive"))
    )
    (net (code "125") (name "unconnected-(X6-R1_7-Pad6)") (class "Default")
      (node (ref "X6") (pin "6") (pinfunction "R1_7_6") (pintype "passive"))
    )
    (net (code "126") (name "unconnected-(X6-R2_5-Pad1)") (class "Default")
      (node (ref "X6") (pin "1") (pinfunction "R2_5_1") (pintype "passive"))
    )
    (net (code "127") (name "unconnected-(X6-R2_6-Pad2)") (class "Default")
      (node (ref "X6") (pin "2") (pinfunction "R2_6_2") (pintype "passive"))
    )
    (net (code "128") (name "unconnected-(X6-R2_7-Pad3)") (class "Default")
      (node (ref "X6") (pin "3") (pinfunction "R2_7_3") (pintype "passive"))
    )
    (net (code "129") (name "unconnected-(X7-R1_5-Pad4)") (class "Default")
      (node (ref "X7") (pin "4") (pinfunction "R1_5_4") (pintype "passive"))
    )
    (net (code "130") (name "unconnected-(X7-R1_6-Pad5)") (class "Default")
      (node (ref "X7") (pin "5") (pinfunction "R1_6_5") (pintype "passive"))
    )
    (net (code "131") (name "unconnected-(X7-R1_7-Pad6)") (class "Default")
      (node (ref "X7") (pin "6") (pinfunction "R1_7_6") (pintype "passive"))
    )
    (net (code "132") (name "unconnected-(X7-R2_5-Pad1)") (class "Default")
      (node (ref "X7") (pin "1") (pinfunction "R2_5_1") (pintype "passive"))
    )
    (net (code "133") (name "unconnected-(X7-R2_6-Pad2)") (class "Default")
      (node (ref "X7") (pin "2") (pinfunction "R2_6_2") (pintype "passive"))
    )
    (net (code "134") (name "unconnected-(X7-R2_7-Pad3)") (class "Default")
      (node (ref "X7") (pin "3") (pinfunction "R2_7_3") (pintype "passive"))
    )
    (net (code "135") (name "unconnected-(X8-R2_5-Pad1)") (class "Default")
      (node (ref "X8") (pin "1") (pinfunction "R2_5_1") (pintype "passive"))
    )
    (net (code "136") (name "unconnected-(X8-R2_6-Pad2)") (class "Default")
      (node (ref "X8") (pin "2") (pinfunction "R2_6_2") (pintype "passive"))
    )
    (net (code "137") (name "unconnected-(X8-R2_7-Pad3)") (class "Default")
      (node (ref "X8") (pin "3") (pinfunction "R2_7_3") (pintype "passive"))
    )
    (net (code "138") (name "unconnected-(X9-+V-Pad3)") (class "Default")
      (node (ref "X9") (pin "3") (pinfunction "+V_3") (pintype "passive"))
    )
    (net (code "139") (name "unconnected-(X9--V-Pad4)") (class "Default")
      (node (ref "X9") (pin "4") (pinfunction "-V_4") (pintype "passive"))
    )
  )
)
